# Main.net
KiCad netlist of a schematic drawn in Altium Designer
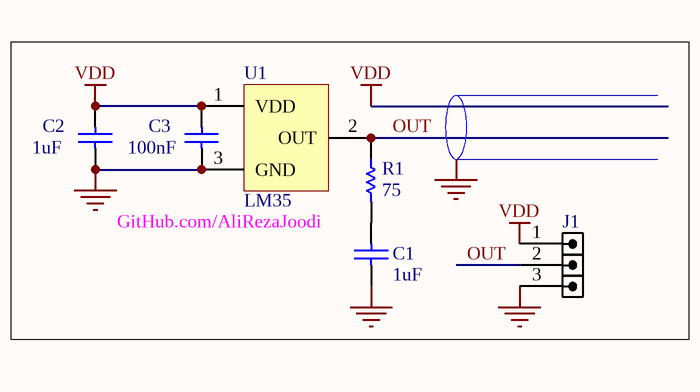
[diagram p0: Main.SchDoc]

(export (version "E")
  (design (tool "Eeschema 10.0.6"))
  (components
    (comp (ref "C1")
      (value "1uF")
      (footprint "0805")
      (description "Capacitor")
      (fields (field (name "MANUFACTURER") "Generic Components") (field (name "PUBLISHER") "Altium Limited"))
      (libsource (lib "Miscellaneous Devices") (part "Cap"))
    )
    (comp (ref "C2")
      (value "1uF")
      (footprint "0805")
      (description "Capacitor")
      (fields (field (name "MANUFACTURER") "Generic Components") (field (name "PUBLISHER") "Altium Limited"))
      (libsource (lib "Miscellaneous Devices") (part "Cap"))
    )
    (comp (ref "C3")
      (value "100nF")
      (footprint "0805")
      (description "Capacitor")
      (fields (field (name "MANUFACTURER") "Generic Components") (field (name "PUBLISHER") "Altium Limited"))
      (libsource (lib "Miscellaneous Devices") (part "Cap"))
    )
    (comp (ref "J1")
      (value "2PIN")
      (footprint "HEADER_THD_STAND_MALE_1X3")
      (description "Connector, Header, 2Pin")
      (libsource (lib "Connector") (part "Connector1x3_Male"))
    )
    (comp (ref "R1")
      (value "75")
      (footprint "0805")
      (description "Resistor")
      (fields (field (name "PUBLISHER") "Altium Limited"))
      (libsource (lib "Miscellaneous Devices") (part "Res1"))
    )
    (comp (ref "U1")
      (value "LM35")
      (footprint "TO92_3Pin_Form6")
      (description "Temperature Sensors")
      (libsource (lib "IC") (part "Sensor_LM35"))
    )
  )
  (nets
    (net (code "1") (name "/OUT") (class "Default")
      (node (ref "J1") (pin "2") (pinfunction "2_2") (pintype "passive"))
      (node (ref "R1") (pin "1") (pinfunction "1_1") (pintype "passive"))
      (node (ref "U1") (pin "2") (pinfunction "OUT_2") (pintype "passive"))
    )
    (net (code "2") (name "GND") (class "Default")
      (node (ref "C1") (pin "1") (pinfunction "1_1") (pintype "passive"))
      (node (ref "C2") (pin "1") (pinfunction "1_1") (pintype "passive"))
      (node (ref "C3") (pin "1") (pinfunction "1_1") (pintype "passive"))
      (node (ref "J1") (pin "3") (pinfunction "3_3") (pintype "passive"))
      (node (ref "U1") (pin "3") (pinfunction "GND_3") (pintype "passive"))
    )
    (net (code "3") (name "Net-(C1-Pad2)") (class "Default")
      (node (ref "C1") (pin "2") (pinfunction "2_2") (pintype "passive"))
      (node (ref "R1") (pin "2") (pinfunction "2_2") (pintype "passive"))
    )
    (net (code "4") (name "VDD") (class "Default")
      (node (ref "C2") (pin "2") (pinfunction "2_2") (pintype "passive"))
      (node (ref "C3") (pin "2") (pinfunction "2_2") (pintype "passive"))
      (node (ref "J1") (pin "1") (pinfunction "1_1") (pintype "passive"))
      (node (ref "U1") (pin "1") (pinfunction "VDD_1") (pintype "passive"))
    )
  )
)
